# SCH_Arduino_Nano_ESP32_CapibaraZero_2024.net
KiCad netlist of a schematic drawn in EasyEDA
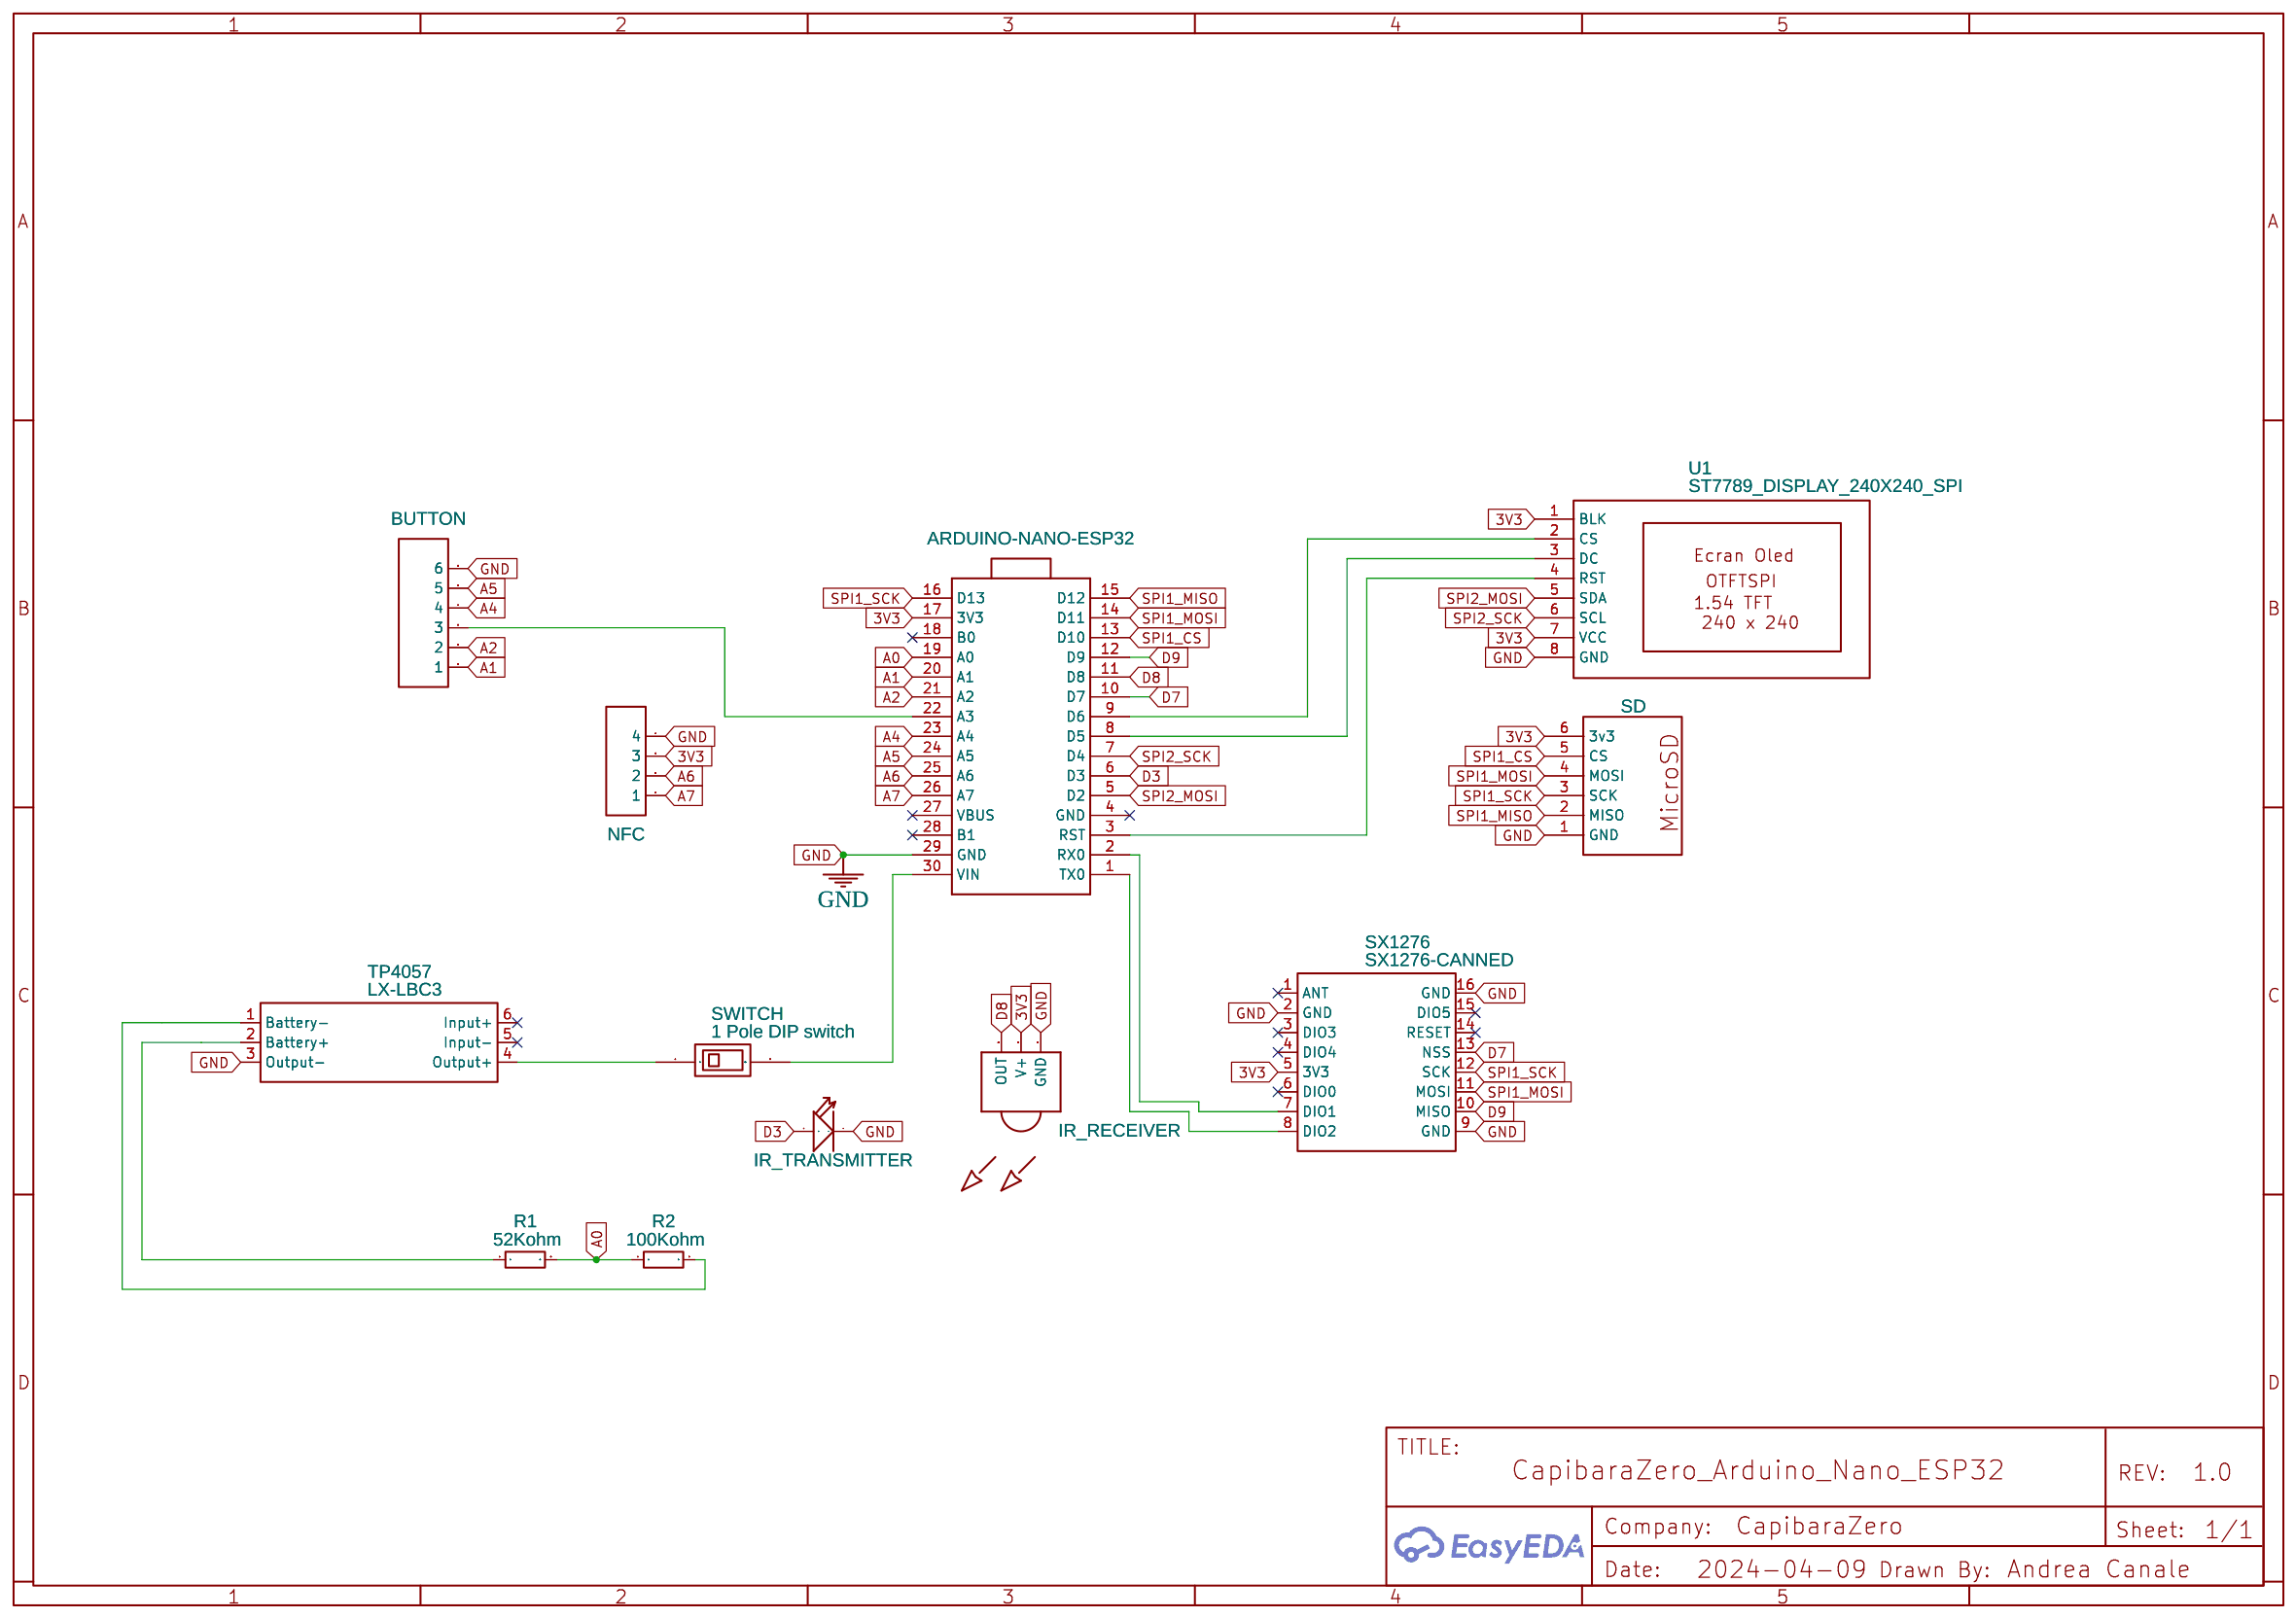
[diagram p0: MainScheme]
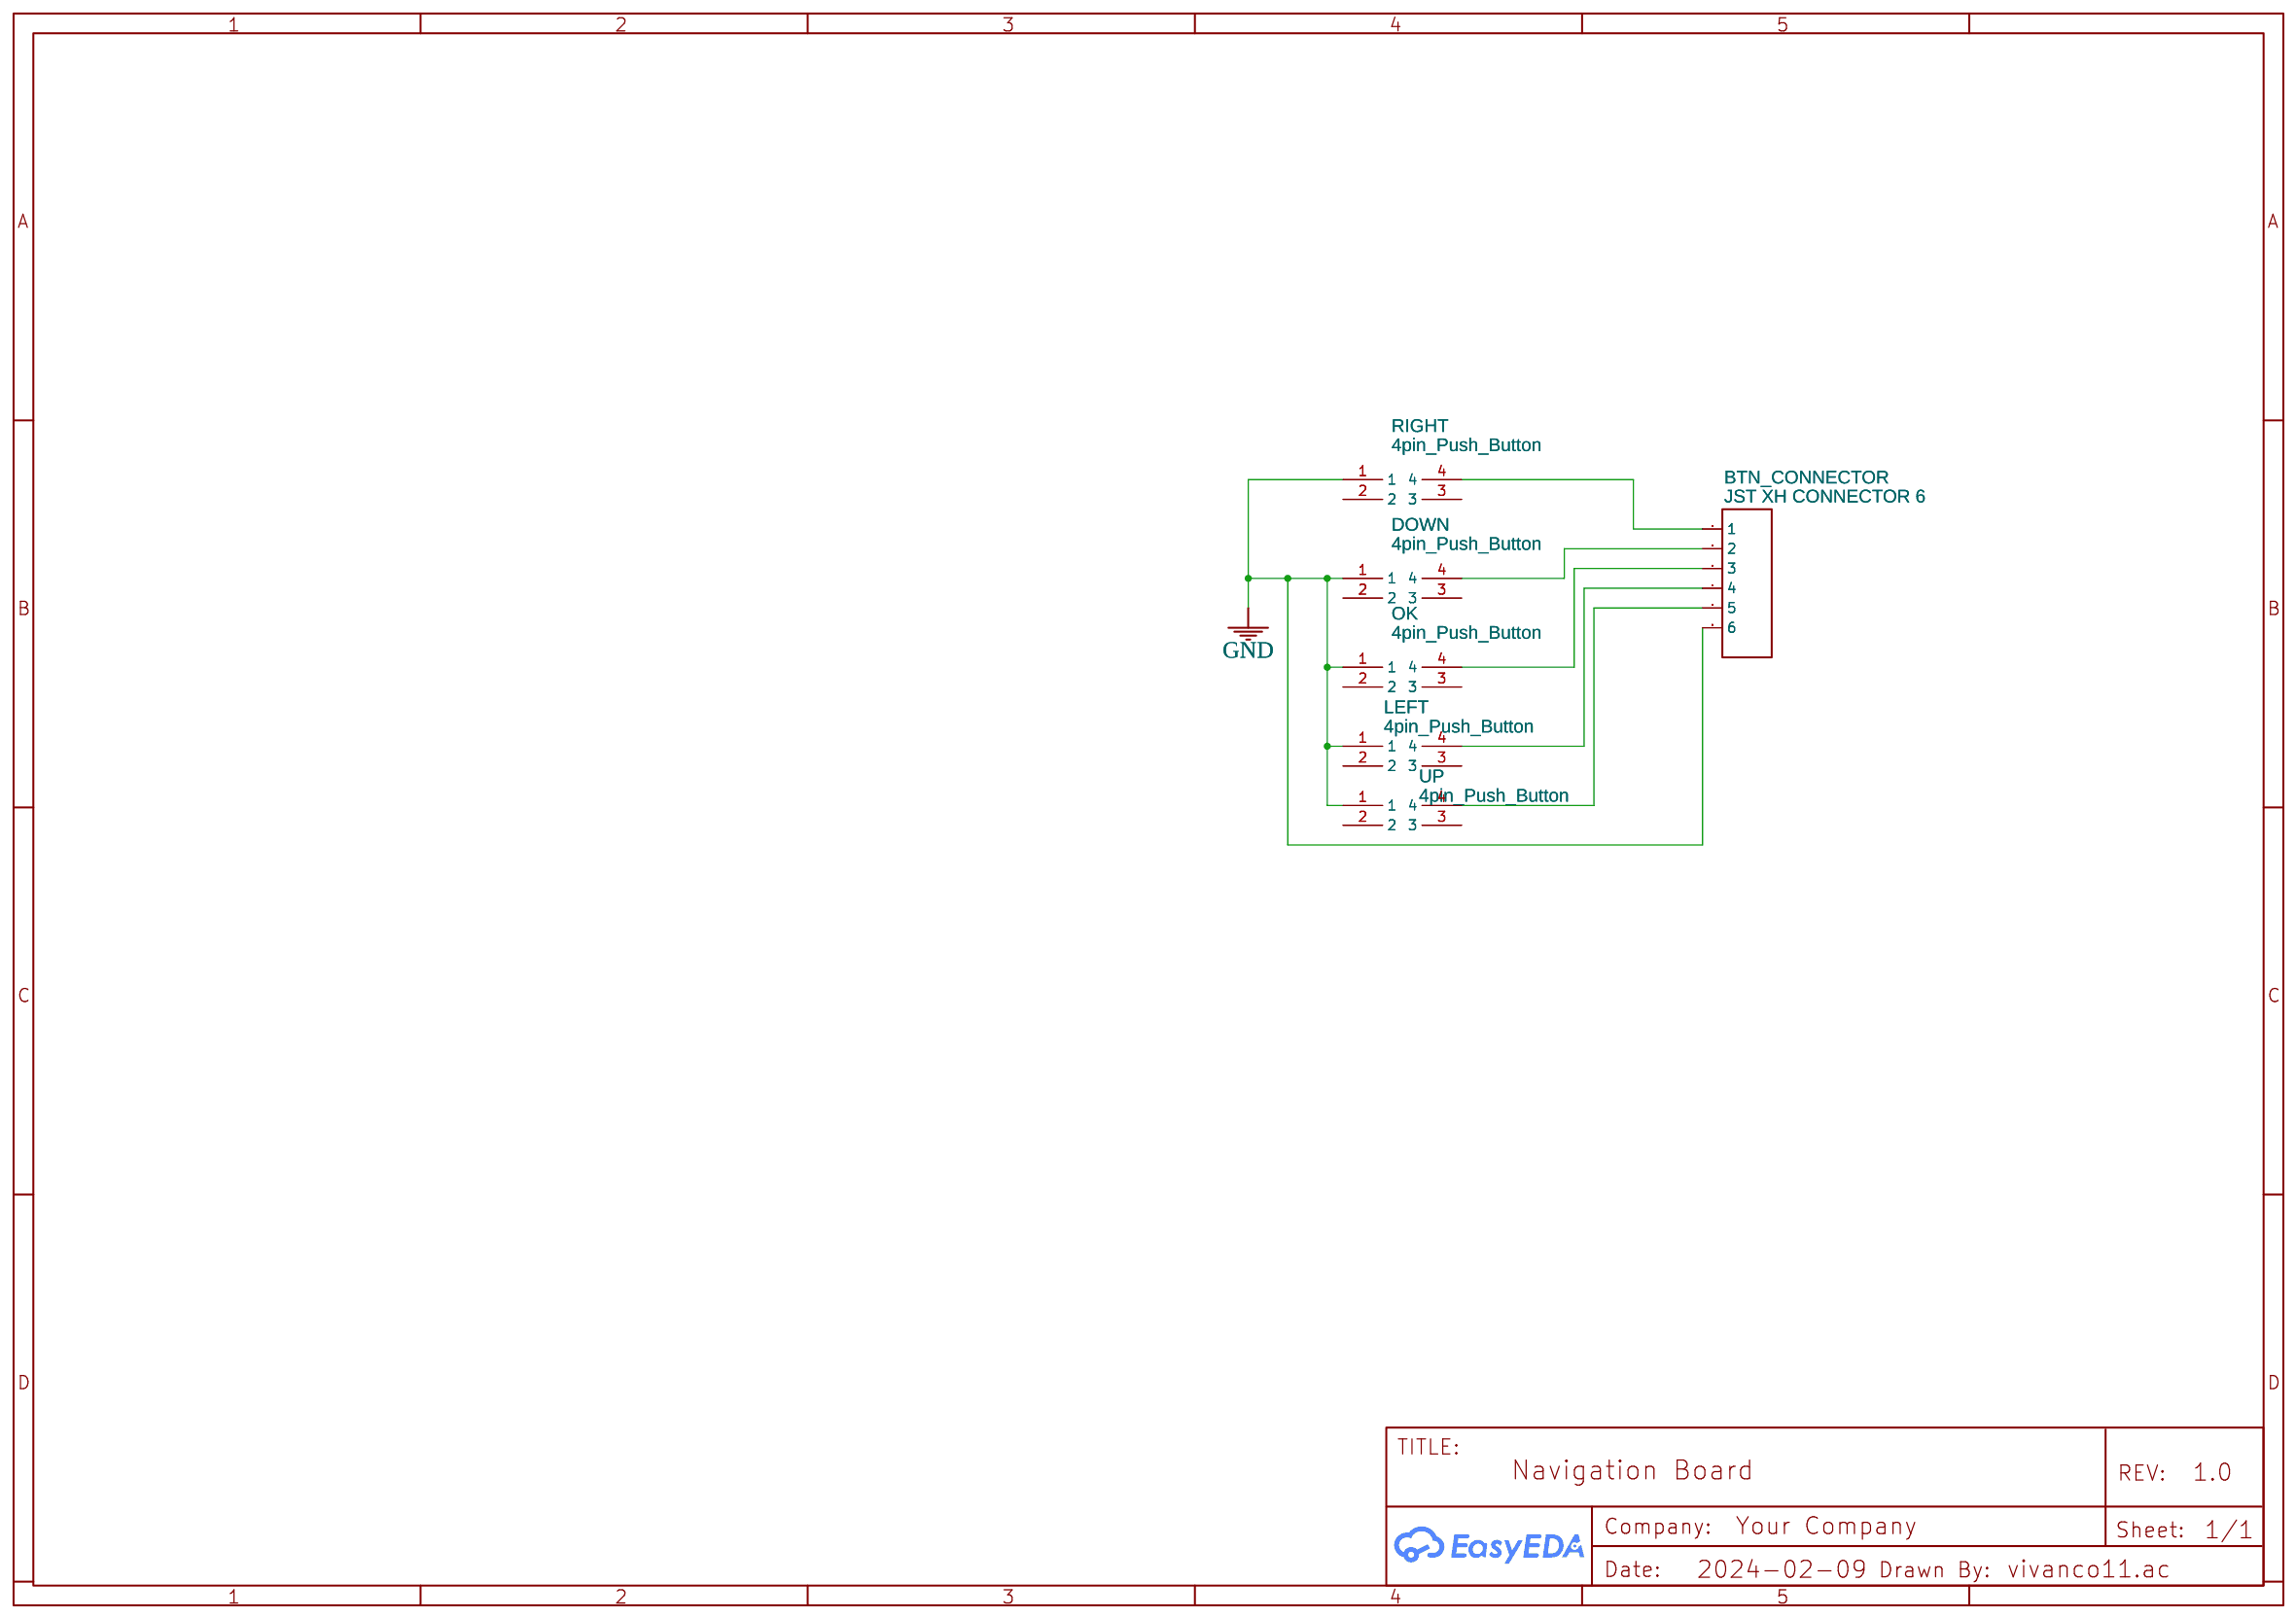
[diagram p1: Navigation_board]

(export (version "E")
  (design (tool "Eeschema 10.0.6"))
  (components
    (comp (ref "ARDUINO-NANO-ESP32")
      (value "ARDUINO-NANO-ESP32")
      (fields (field (name "Manufacturer") "Arduino"))
      (libsource (lib "") (part "ARDUINO-NANO-ESP32"))
    )
    (comp (ref "BUTTON")
      (value "BTN Connector")
      (fields (field (name "Manufacturer Part") "JST_XH CONNECTOR"))
      (libsource (lib "") (part "JST XH CONNECTOR 6"))
    )
    (comp (ref "IR_RECEIVER") (value "IR Receiver") (libsource (lib "") (part "IR TRANSMITTER")))
    (comp (ref "IR_TRANSMITTER")
      (value "DIP-IR-LED-940NM(2P-D5MM)")
      (fields (field (name "Manufacturer Part") "IR523B-W60W1"))
      (libsource (lib "") (part "DIP-IR-LED-940NM(2P-D5MM)"))
    )
    (comp (ref "NFC")
      (value "NFC Connector")
      (fields (field (name "Manufacturer Part") "JST_XH CONNECTOR"))
      (libsource (lib "") (part "JST XH CONNECTOR 4"))
    )
    (comp (ref "R1")
      (value "52Kohm")
      (fields
        (field (name "Manufacturer Part") "EWWR0001J20R0T9")
        (field (name "Manufacturer") "ResistorToday")
      )
      (libsource (lib "") (part "Resistor Normal"))
    )
    (comp (ref "R2")
      (value "100Kohm")
      (fields
        (field (name "Manufacturer Part") "EWWR0001J20R0T9")
        (field (name "Manufacturer") "ResistorToday")
      )
      (libsource (lib "") (part "Resistor Normal"))
    )
    (comp (ref "SD") (value "MicroSDSPI") (libsource (lib "") (part "MicroSDSPI")))
    (comp (ref "SWITCH") (value "1 Pole DIP switch") (libsource (lib "") (part "1 Pole DIP switch")))
    (comp (ref "SX1276")
      (value "SX1276-CANNED")
      (fields (field (name "Manufacturer Part") "LoRa1276-C1") (field (name "Manufacturer") "G-NiceRF"))
      (libsource (lib "") (part "SX1276-CANNED"))
    )
    (comp (ref "TP4057") (value "LX-LBC3") (libsource (lib "") (part "LX-LBC3")))
    (comp (ref "U1")
      (value "ST7789_DISPLAY_240X240_SPI")
      (libsource (lib "") (part "ST7789_DISPLAY_240X240_SPI"))
    )
    (comp (ref "BTN_CONNECTOR")
      (value "JST XH CONNECTOR 6")
      (fields (field (name "Manufacturer Part") "JST_XH CONNECTOR"))
      (libsource (lib "") (part "JST XH CONNECTOR 6"))
    )
    (comp (ref "DOWN") (value "4pin_Push_Button") (libsource (lib "") (part "4pin_Push_Button_1")))
    (comp (ref "LEFT") (value "4pin_Push_Button") (libsource (lib "") (part "4pin_Push_Button")))
    (comp (ref "OK") (value "4pin_Push_Button") (libsource (lib "") (part "4pin_Push_Button_4")))
    (comp (ref "RIGHT") (value "4pin_Push_Button") (libsource (lib "") (part "4pin_Push_Button_3")))
    (comp (ref "UP") (value "4pin_Push_Button") (libsource (lib "") (part "4pin_Push_Button_2")))
  )
  (nets
    (net (code "1") (name "3V3") (class "Default")
      (node (ref "ARDUINO-NANO-ESP32") (pin "17") (pinfunction "3V3_17") (pintype "unspecified"))
      (node (ref "IR_RECEIVER") (pin "VCC") (pinfunction "V+_VCC") (pintype "unspecified"))
      (node (ref "NFC") (pin "3") (pinfunction "3_3") (pintype "unspecified"))
      (node (ref "SD") (pin "6") (pinfunction "3v3_6") (pintype "unspecified"))
      (node (ref "SX1276") (pin "5") (pinfunction "3V3_5") (pintype "unspecified"))
      (node (ref "U1") (pin "1") (pinfunction "BLK_1") (pintype "unspecified"))
      (node (ref "U1") (pin "7") (pinfunction "VCC_7") (pintype "unspecified"))
    )
    (net (code "2") (name "A0") (class "Default")
      (node (ref "ARDUINO-NANO-ESP32") (pin "19") (pinfunction "A0_19") (pintype "unspecified"))
      (node (ref "R1") (pin "2") (pinfunction "2_2") (pintype "unspecified"))
      (node (ref "R2") (pin "1") (pinfunction "1_1") (pintype "unspecified"))
    )
    (net (code "3") (name "A1") (class "Default")
      (node (ref "ARDUINO-NANO-ESP32") (pin "20") (pinfunction "A1_20") (pintype "unspecified"))
      (node (ref "BUTTON") (pin "1") (pinfunction "1_1") (pintype "unspecified"))
    )
    (net (code "4") (name "A2") (class "Default")
      (node (ref "ARDUINO-NANO-ESP32") (pin "21") (pinfunction "A2_21") (pintype "unspecified"))
      (node (ref "BUTTON") (pin "2") (pinfunction "2_2") (pintype "unspecified"))
    )
    (net (code "5") (name "A4") (class "Default")
      (node (ref "ARDUINO-NANO-ESP32") (pin "23") (pinfunction "A4_23") (pintype "unspecified"))
      (node (ref "BUTTON") (pin "4") (pinfunction "4_4") (pintype "unspecified"))
    )
    (net (code "6") (name "A5") (class "Default")
      (node (ref "ARDUINO-NANO-ESP32") (pin "24") (pinfunction "A5_24") (pintype "unspecified"))
      (node (ref "BUTTON") (pin "5") (pinfunction "5_5") (pintype "unspecified"))
    )
    (net (code "7") (name "A6") (class "Default")
      (node (ref "ARDUINO-NANO-ESP32") (pin "25") (pinfunction "A6_25") (pintype "unspecified"))
      (node (ref "NFC") (pin "2") (pinfunction "2_2") (pintype "unspecified"))
    )
    (net (code "8") (name "A7") (class "Default")
      (node (ref "ARDUINO-NANO-ESP32") (pin "26") (pinfunction "A7_26") (pintype "unspecified"))
      (node (ref "NFC") (pin "1") (pinfunction "1_1") (pintype "unspecified"))
    )
    (net (code "9") (name "D3") (class "Default")
      (node (ref "ARDUINO-NANO-ESP32") (pin "6") (pinfunction "D3_6") (pintype "unspecified"))
      (node (ref "IR_TRANSMITTER") (pin "+") (pinfunction "+_+") (pintype "unspecified"))
    )
    (net (code "10") (name "D7") (class "Default")
      (node (ref "ARDUINO-NANO-ESP32") (pin "10") (pinfunction "D7_10") (pintype "unspecified"))
      (node (ref "SX1276") (pin "13") (pinfunction "NSS_13") (pintype "unspecified"))
    )
    (net (code "11") (name "D8") (class "Default")
      (node (ref "ARDUINO-NANO-ESP32") (pin "11") (pinfunction "D8_11") (pintype "unspecified"))
      (node (ref "IR_RECEIVER") (pin "OUT") (pinfunction "OUT_OUT") (pintype "unspecified"))
    )
    (net (code "12") (name "D9") (class "Default")
      (node (ref "ARDUINO-NANO-ESP32") (pin "12") (pinfunction "D9_12") (pintype "unspecified"))
      (node (ref "SX1276") (pin "10") (pinfunction "MISO_10") (pintype "unspecified"))
    )
    (net (code "13") (name "GND") (class "Default")
      (node (ref "ARDUINO-NANO-ESP32") (pin "29") (pinfunction "GND_29") (pintype "unspecified"))
      (node (ref "BTN_CONNECTOR") (pin "6") (pinfunction "6_6") (pintype "unspecified"))
      (node (ref "BUTTON") (pin "6") (pinfunction "6_6") (pintype "unspecified"))
      (node (ref "DOWN") (pin "1") (pinfunction "1_1") (pintype "unspecified"))
      (node (ref "IR_RECEIVER") (pin "GND") (pinfunction "GND_GND") (pintype "unspecified"))
      (node (ref "IR_TRANSMITTER") (pin "-") (pinfunction "-_-") (pintype "unspecified"))
      (node (ref "LEFT") (pin "1") (pinfunction "1_1") (pintype "unspecified"))
      (node (ref "NFC") (pin "4") (pinfunction "4_4") (pintype "unspecified"))
      (node (ref "OK") (pin "1") (pinfunction "1_1") (pintype "unspecified"))
      (node (ref "RIGHT") (pin "1") (pinfunction "1_1") (pintype "unspecified"))
      (node (ref "SD") (pin "1") (pinfunction "GND_1") (pintype "unspecified"))
      (node (ref "SX1276") (pin "16") (pinfunction "GND_16") (pintype "unspecified"))
      (node (ref "SX1276") (pin "2") (pinfunction "GND_2") (pintype "unspecified"))
      (node (ref "SX1276") (pin "9") (pinfunction "GND_9") (pintype "unspecified"))
      (node (ref "TP4057") (pin "3") (pinfunction "Output-_3") (pintype "unspecified"))
      (node (ref "U1") (pin "8") (pinfunction "GND_8") (pintype "unspecified"))
      (node (ref "UP") (pin "1") (pinfunction "1_1") (pintype "unspecified"))
    )
    (net (code "14") (name "Net-(ARDUINO-NANO-ESP32-A3)") (class "Default")
      (node (ref "ARDUINO-NANO-ESP32") (pin "22") (pinfunction "A3_22") (pintype "unspecified"))
      (node (ref "BUTTON") (pin "3") (pinfunction "3_3") (pintype "unspecified"))
    )
    (net (code "15") (name "Net-(ARDUINO-NANO-ESP32-D5)") (class "Default")
      (node (ref "ARDUINO-NANO-ESP32") (pin "8") (pinfunction "D5_8") (pintype "unspecified"))
      (node (ref "U1") (pin "3") (pinfunction "DC_3") (pintype "unspecified"))
    )
    (net (code "16") (name "Net-(ARDUINO-NANO-ESP32-D6)") (class "Default")
      (node (ref "ARDUINO-NANO-ESP32") (pin "9") (pinfunction "D6_9") (pintype "unspecified"))
      (node (ref "U1") (pin "2") (pinfunction "CS_2") (pintype "unspecified"))
    )
    (net (code "17") (name "Net-(ARDUINO-NANO-ESP32-RST)") (class "Default")
      (node (ref "ARDUINO-NANO-ESP32") (pin "3") (pinfunction "RST_3") (pintype "unspecified"))
      (node (ref "U1") (pin "4") (pinfunction "RST_4") (pintype "unspecified"))
    )
    (net (code "18") (name "Net-(ARDUINO-NANO-ESP32-RX0)") (class "Default")
      (node (ref "ARDUINO-NANO-ESP32") (pin "2") (pinfunction "RX0_2") (pintype "unspecified"))
      (node (ref "SX1276") (pin "7") (pinfunction "DIO1_7") (pintype "unspecified"))
    )
    (net (code "19") (name "Net-(ARDUINO-NANO-ESP32-TX0)") (class "Default")
      (node (ref "ARDUINO-NANO-ESP32") (pin "1") (pinfunction "TX0_1") (pintype "unspecified"))
      (node (ref "SX1276") (pin "8") (pinfunction "DIO2_8") (pintype "unspecified"))
    )
    (net (code "20") (name "Net-(ARDUINO-NANO-ESP32-VIN)") (class "Default")
      (node (ref "ARDUINO-NANO-ESP32") (pin "30") (pinfunction "VIN_30") (pintype "unspecified"))
      (node (ref "SWITCH") (pin "2") (pinfunction "OUT_2") (pintype "unspecified"))
    )
    (net (code "21") (name "Net-(BTN_CONNECTOR-Pad1)") (class "Default")
      (node (ref "BTN_CONNECTOR") (pin "1") (pinfunction "1_1") (pintype "unspecified"))
      (node (ref "RIGHT") (pin "4") (pinfunction "4_4") (pintype "unspecified"))
    )
    (net (code "22") (name "Net-(BTN_CONNECTOR-Pad2)") (class "Default")
      (node (ref "BTN_CONNECTOR") (pin "2") (pinfunction "2_2") (pintype "unspecified"))
      (node (ref "DOWN") (pin "4") (pinfunction "4_4") (pintype "unspecified"))
    )
    (net (code "23") (name "Net-(BTN_CONNECTOR-Pad3)") (class "Default")
      (node (ref "BTN_CONNECTOR") (pin "3") (pinfunction "3_3") (pintype "unspecified"))
      (node (ref "OK") (pin "4") (pinfunction "4_4") (pintype "unspecified"))
    )
    (net (code "24") (name "Net-(BTN_CONNECTOR-Pad4)") (class "Default")
      (node (ref "BTN_CONNECTOR") (pin "4") (pinfunction "4_4") (pintype "unspecified"))
      (node (ref "LEFT") (pin "4") (pinfunction "4_4") (pintype "unspecified"))
    )
    (net (code "25") (name "Net-(BTN_CONNECTOR-Pad5)") (class "Default")
      (node (ref "BTN_CONNECTOR") (pin "5") (pinfunction "5_5") (pintype "unspecified"))
      (node (ref "UP") (pin "4") (pinfunction "4_4") (pintype "unspecified"))
    )
    (net (code "26") (name "Net-(SWITCH-IN)") (class "Default")
      (node (ref "SWITCH") (pin "1") (pinfunction "IN_1") (pintype "unspecified"))
      (node (ref "TP4057") (pin "4") (pinfunction "Output+_4") (pintype "unspecified"))
    )
    (net (code "27") (name "Net-(TP4057-Battery+)") (class "Default")
      (node (ref "R1") (pin "1") (pinfunction "1_1") (pintype "unspecified"))
      (node (ref "TP4057") (pin "2") (pinfunction "Battery+_2") (pintype "unspecified"))
    )
    (net (code "28") (name "Net-(TP4057-Battery-)") (class "Default")
      (node (ref "R2") (pin "2") (pinfunction "2_2") (pintype "unspecified"))
      (node (ref "TP4057") (pin "1") (pinfunction "Battery-_1") (pintype "unspecified"))
    )
    (net (code "29") (name "SPI1_CS") (class "Default")
      (node (ref "ARDUINO-NANO-ESP32") (pin "13") (pinfunction "D10_13") (pintype "unspecified"))
      (node (ref "SD") (pin "5") (pinfunction "CS_5") (pintype "unspecified"))
    )
    (net (code "30") (name "SPI1_MISO") (class "Default")
      (node (ref "ARDUINO-NANO-ESP32") (pin "15") (pinfunction "D12_15") (pintype "unspecified"))
      (node (ref "SD") (pin "2") (pinfunction "MISO_2") (pintype "unspecified"))
    )
    (net (code "31") (name "SPI1_MOSI") (class "Default")
      (node (ref "ARDUINO-NANO-ESP32") (pin "14") (pinfunction "D11_14") (pintype "unspecified"))
      (node (ref "SD") (pin "4") (pinfunction "MOSI_4") (pintype "unspecified"))
      (node (ref "SX1276") (pin "11") (pinfunction "MOSI_11") (pintype "unspecified"))
    )
    (net (code "32") (name "SPI1_SCK") (class "Default")
      (node (ref "ARDUINO-NANO-ESP32") (pin "16") (pinfunction "D13_16") (pintype "unspecified"))
      (node (ref "SD") (pin "3") (pinfunction "SCK_3") (pintype "unspecified"))
      (node (ref "SX1276") (pin "12") (pinfunction "SCK_12") (pintype "unspecified"))
    )
    (net (code "33") (name "SPI2_MOSI") (class "Default")
      (node (ref "ARDUINO-NANO-ESP32") (pin "5") (pinfunction "D2_5") (pintype "unspecified"))
      (node (ref "U1") (pin "5") (pinfunction "SDA_5") (pintype "unspecified"))
    )
    (net (code "34") (name "SPI2_SCK") (class "Default")
      (node (ref "ARDUINO-NANO-ESP32") (pin "7") (pinfunction "D4_7") (pintype "unspecified"))
      (node (ref "U1") (pin "6") (pinfunction "SCL_6") (pintype "unspecified"))
    )
    (net (code "35") (name "unconnected-(ARDUINO-NANO-ESP32-B0-Pad18)") (class "Default")
      (node (ref "ARDUINO-NANO-ESP32") (pin "18") (pinfunction "B0_18") (pintype "unspecified+no_connect"))
    )
    (net (code "36") (name "unconnected-(ARDUINO-NANO-ESP32-B1-Pad28)") (class "Default")
      (node (ref "ARDUINO-NANO-ESP32") (pin "28") (pinfunction "B1_28") (pintype "unspecified+no_connect"))
    )
    (net (code "37") (name "unconnected-(ARDUINO-NANO-ESP32-GND-Pad4)") (class "Default")
      (node (ref "ARDUINO-NANO-ESP32") (pin "4") (pinfunction "GND_4") (pintype "unspecified+no_connect"))
    )
    (net (code "38") (name "unconnected-(ARDUINO-NANO-ESP32-VBUS-Pad27)") (class "Default")
      (node (ref "ARDUINO-NANO-ESP32") (pin "27") (pinfunction "VBUS_27") (pintype "unspecified+no_connect"))
    )
    (net (code "39") (name "unconnected-(DOWN-Pad2)") (class "Default")
      (node (ref "DOWN") (pin "2") (pinfunction "2_2") (pintype "unspecified"))
    )
    (net (code "40") (name "unconnected-(DOWN-Pad3)") (class "Default")
      (node (ref "DOWN") (pin "3") (pinfunction "3_3") (pintype "unspecified"))
    )
    (net (code "41") (name "unconnected-(LEFT-Pad2)") (class "Default")
      (node (ref "LEFT") (pin "2") (pinfunction "2_2") (pintype "unspecified"))
    )
    (net (code "42") (name "unconnected-(LEFT-Pad3)") (class "Default")
      (node (ref "LEFT") (pin "3") (pinfunction "3_3") (pintype "unspecified"))
    )
    (net (code "43") (name "unconnected-(OK-Pad2)") (class "Default")
      (node (ref "OK") (pin "2") (pinfunction "2_2") (pintype "unspecified"))
    )
    (net (code "44") (name "unconnected-(OK-Pad3)") (class "Default")
      (node (ref "OK") (pin "3") (pinfunction "3_3") (pintype "unspecified"))
    )
    (net (code "45") (name "unconnected-(RIGHT-Pad2)") (class "Default")
      (node (ref "RIGHT") (pin "2") (pinfunction "2_2") (pintype "unspecified"))
    )
    (net (code "46") (name "unconnected-(RIGHT-Pad3)") (class "Default")
      (node (ref "RIGHT") (pin "3") (pinfunction "3_3") (pintype "unspecified"))
    )
    (net (code "47") (name "unconnected-(SX1276-ANT-Pad1)") (class "Default")
      (node (ref "SX1276") (pin "1") (pinfunction "ANT_1") (pintype "unspecified+no_connect"))
    )
    (net (code "48") (name "unconnected-(SX1276-DIO0-Pad6)") (class "Default")
      (node (ref "SX1276") (pin "6") (pinfunction "DIO0_6") (pintype "unspecified+no_connect"))
    )
    (net (code "49") (name "unconnected-(SX1276-DIO3-Pad3)") (class "Default")
      (node (ref "SX1276") (pin "3") (pinfunction "DIO3_3") (pintype "unspecified+no_connect"))
    )
    (net (code "50") (name "unconnected-(SX1276-DIO4-Pad4)") (class "Default")
      (node (ref "SX1276") (pin "4") (pinfunction "DIO4_4") (pintype "unspecified+no_connect"))
    )
    (net (code "51") (name "unconnected-(SX1276-DIO5-Pad15)") (class "Default")
      (node (ref "SX1276") (pin "15") (pinfunction "DIO5_15") (pintype "unspecified+no_connect"))
    )
    (net (code "52") (name "unconnected-(SX1276-RESET-Pad14)") (class "Default")
      (node (ref "SX1276") (pin "14") (pinfunction "RESET_14") (pintype "unspecified+no_connect"))
    )
    (net (code "53") (name "unconnected-(TP4057-Input+-Pad6)") (class "Default")
      (node (ref "TP4057") (pin "6") (pinfunction "Input+_6") (pintype "unspecified+no_connect"))
    )
    (net (code "54") (name "unconnected-(TP4057-Input--Pad5)") (class "Default")
      (node (ref "TP4057") (pin "5") (pinfunction "Input-_5") (pintype "unspecified+no_connect"))
    )
    (net (code "55") (name "unconnected-(UP-Pad2)") (class "Default")
      (node (ref "UP") (pin "2") (pinfunction "2_2") (pintype "unspecified"))
    )
    (net (code "56") (name "unconnected-(UP-Pad3)") (class "Default")
      (node (ref "UP") (pin "3") (pinfunction "3_3") (pintype "unspecified"))
    )
  )
)
